# SCHEMATIC.net
KiCad netlist of a schematic drawn in Altium Designer
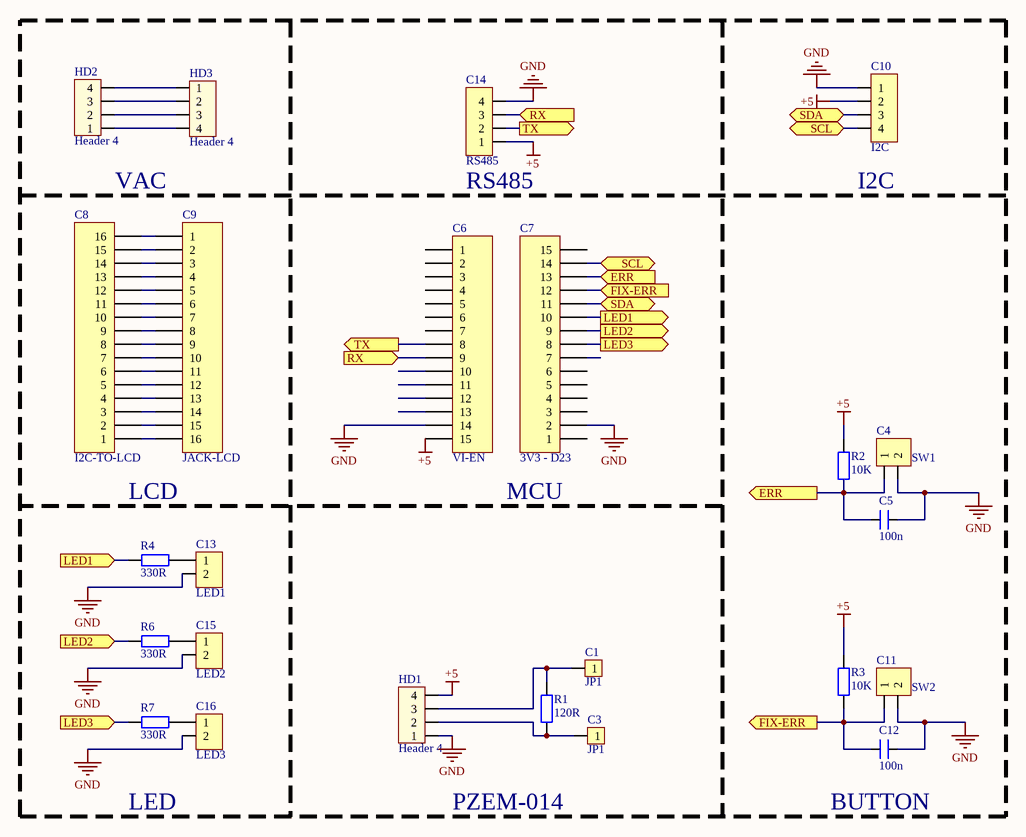
[diagram p0: SCHEMATIC.SchDoc]

(export (version "E")
  (design (tool "Eeschema 10.0.6"))
  (components
    (comp (ref "C1")
      (value "JP1")
      (footprint "JP1-D1T")
      (description "WR-PHD 2.54 mm Angled Socket Header")
      (fields
        (field (name "MANUFACTURER") "Würth Elektronik eiSos GmbH")
        (field (name "PARTNO") "613002143121")
        (field (name "CREATED BY") "Karrer Zheng")
      )
      (libsource (lib "LIBRARY") (part "JP1"))
    )
    (comp (ref "C3")
      (value "JP1")
      (footprint "JP1-D1T")
      (description "WR-PHD 2.54 mm Angled Socket Header")
      (fields
        (field (name "MANUFACTURER") "Würth Elektronik eiSos GmbH")
        (field (name "PARTNO") "613002143121")
        (field (name "CREATED BY") "Karrer Zheng")
      )
      (libsource (lib "LIBRARY") (part "JP1"))
    )
    (comp (ref "C4")
      (value "SW1")
      (footprint "Header2")
      (description "Header IDC, 2 x 1 Pin Vertical 2.54mm Pitch (Non-Boxed, Male)")
      (fields
        (field (name "MANUFACTURER") "Würth Elektronik eiSos GmbH")
        (field (name "PARTNO") "613002143121")
        (field (name "CREATED BY") "Karrer Zheng")
      )
      (libsource (lib "LIBRARY") (part "Header2"))
    )
    (comp (ref "C5")
      (value "100n")
      (footprint "SM-0805")
      (description "Cap SMD")
      (libsource (lib "echipkool-com-library") (part "CM"))
    )
    (comp (ref "C6")
      (value "VI-EN")
      (footprint "JP15-C1T")
      (description "WR-PHD 2.54 mm Angled Socket Header")
      (fields
        (field (name "MANUFACTURER") "Würth Elektronik eiSos GmbH")
        (field (name "PARTNO") "613015143121")
        (field (name "CREATED BY") "Karrer Zheng")
      )
      (libsource (lib "") (part "JP15_1"))
    )
    (comp (ref "C7")
      (value "3V3 - D23")
      (footprint "JP15-C1T")
      (description "WR-PHD 2.54 mm Angled Socket Header")
      (fields
        (field (name "MANUFACTURER") "Würth Elektronik eiSos GmbH")
        (field (name "PARTNO") "613015143121")
        (field (name "CREATED BY") "Karrer Zheng")
      )
      (libsource (lib "LIBRARY") (part "JP15"))
    )
    (comp (ref "C8")
      (value "I2C-TO-LCD")
      (footprint "JP16-C1T")
      (description "WR-PHD 2.54 mm Angled Socket Header")
      (fields
        (field (name "MANUFACTURER") "Würth Elektronik eiSos GmbH")
        (field (name "PARTNO") "613016143121")
        (field (name "CREATED BY") "Karrer Zheng")
      )
      (libsource (lib "") (part "JP16_1"))
    )
    (comp (ref "C9")
      (value "JACK-LCD")
      (footprint "JP16-C1T")
      (description "WR-PHD 2.54 mm Angled Socket Header")
      (fields
        (field (name "MANUFACTURER") "Würth Elektronik eiSos GmbH")
        (field (name "PARTNO") "613016143121")
        (field (name "CREATED BY") "Karrer Zheng")
      )
      (libsource (lib "LIBRARY") (part "JP16"))
    )
    (comp (ref "C10")
      (value "I2C")
      (footprint "JP4-C1T")
      (description "WR-PHD 2.54 mm Angled Socket Header")
      (fields
        (field (name "MANUFACTURER") "Würth Elektronik eiSos GmbH")
        (field (name "PARTNO") "613004143121")
        (field (name "CREATED BY") "Karrer Zheng")
      )
      (libsource (lib "") (part "JP4_1"))
    )
    (comp (ref "C11")
      (value "SW2")
      (footprint "Header2")
      (description "Header IDC, 2 x 1 Pin Vertical 2.54mm Pitch (Non-Boxed, Male)")
      (fields
        (field (name "MANUFACTURER") "Würth Elektronik eiSos GmbH")
        (field (name "PARTNO") "613002143121")
        (field (name "CREATED BY") "Karrer Zheng")
      )
      (libsource (lib "LIBRARY") (part "Header2"))
    )
    (comp (ref "C12")
      (value "100n")
      (footprint "SM-0805")
      (description "Cap SMD")
      (libsource (lib "echipkool-com-library") (part "CM"))
    )
    (comp (ref "C13")
      (value "LED1")
      (footprint "Header2")
      (description "Header IDC, 2 x 1 Pin Vertical 2.54mm Pitch (Non-Boxed, Male)")
      (fields
        (field (name "MANUFACTURER") "Würth Elektronik eiSos GmbH")
        (field (name "PARTNO") "613002143121")
        (field (name "CREATED BY") "Karrer Zheng")
      )
      (libsource (lib "") (part "Header2_1"))
    )
    (comp (ref "C14")
      (value "RS485")
      (footprint "JP4-C1T")
      (description "WR-PHD 2.54 mm Angled Socket Header")
      (fields
        (field (name "MANUFACTURER") "Würth Elektronik eiSos GmbH")
        (field (name "PARTNO") "613004143121")
        (field (name "CREATED BY") "Karrer Zheng")
      )
      (libsource (lib "LIBRARY") (part "JP4"))
    )
    (comp (ref "C15")
      (value "LED2")
      (footprint "Header2")
      (description "Header IDC, 2 x 1 Pin Vertical 2.54mm Pitch (Non-Boxed, Male)")
      (fields
        (field (name "MANUFACTURER") "Würth Elektronik eiSos GmbH")
        (field (name "PARTNO") "613002143121")
        (field (name "CREATED BY") "Karrer Zheng")
      )
      (libsource (lib "") (part "Header2_1"))
    )
    (comp (ref "C16")
      (value "LED3")
      (footprint "Header2")
      (description "Header IDC, 2 x 1 Pin Vertical 2.54mm Pitch (Non-Boxed, Male)")
      (fields
        (field (name "MANUFACTURER") "Würth Elektronik eiSos GmbH")
        (field (name "PARTNO") "613002143121")
        (field (name "CREATED BY") "Karrer Zheng")
      )
      (libsource (lib "") (part "Header2_1"))
    )
    (comp (ref "HD1")
      (value "Header 4")
      (footprint "HED4")
      (description "Header 4 (Green)")
      (libsource (lib "syhaunguyen") (part "Hed4"))
    )
    (comp (ref "HD2")
      (value "Header 4")
      (footprint "HED4")
      (description "Header 4 (Green)")
      (libsource (lib "syhaunguyen") (part "Hed4"))
    )
    (comp (ref "HD3")
      (value "Header 4")
      (footprint "HED4T")
      (description "Header 4 (Green)")
      (libsource (lib "") (part "Hed4_1"))
    )
    (comp (ref "R1")
      (value "120R")
      (footprint "SM-RES-0805")
      (description "Resistor 1/4W")
      (libsource (lib "echipkool-com-library") (part "R1/4W"))
    )
    (comp (ref "R2")
      (value "10K")
      (footprint "SM-RES-0805")
      (description "Resistor 1/4W")
      (libsource (lib "echipkool-com-library") (part "R1/4W"))
    )
    (comp (ref "R3")
      (value "10K")
      (footprint "SM-RES-0805")
      (description "Resistor 1/4W")
      (libsource (lib "echipkool-com-library") (part "R1/4W"))
    )
    (comp (ref "R4")
      (value "330R")
      (footprint "SM-RES-0805")
      (description "Resistor 1/4W")
      (libsource (lib "echipkool-com-library") (part "R1/4W"))
    )
    (comp (ref "R6")
      (value "330R")
      (footprint "SM-RES-0805")
      (description "Resistor 1/4W")
      (libsource (lib "echipkool-com-library") (part "R1/4W"))
    )
    (comp (ref "R7")
      (value "330R")
      (footprint "SM-RES-0805")
      (description "Resistor 1/4W")
      (libsource (lib "echipkool-com-library") (part "R1/4W"))
    )
  )
  (nets
    (net (code "1") (name "+5") (class "Default")
      (node (ref "C10") (pin "2") (pinfunction "2_2") (pintype "passive"))
      (node (ref "C14") (pin "1") (pinfunction "1_1") (pintype "passive"))
      (node (ref "C6") (pin "15") (pinfunction "15_15") (pintype "passive"))
      (node (ref "HD1") (pin "4") (pinfunction "4_4") (pintype "passive"))
      (node (ref "R2") (pin "1") (pinfunction "1_1") (pintype "passive"))
      (node (ref "R3") (pin "1") (pinfunction "1_1") (pintype "passive"))
    )
    (net (code "2") (name "/ERR") (class "Default")
      (node (ref "C4") (pin "1") (pinfunction "1_1") (pintype "passive"))
      (node (ref "C5") (pin "2") (pinfunction "2_2") (pintype "passive"))
      (node (ref "C7") (pin "13") (pinfunction "13_13") (pintype "passive"))
      (node (ref "R2") (pin "2") (pinfunction "2_2") (pintype "passive"))
    )
    (net (code "3") (name "/FIX-ERR") (class "Default")
      (node (ref "C11") (pin "1") (pinfunction "1_1") (pintype "passive"))
      (node (ref "C12") (pin "2") (pinfunction "2_2") (pintype "passive"))
      (node (ref "C7") (pin "12") (pinfunction "12_12") (pintype "passive"))
      (node (ref "R3") (pin "2") (pinfunction "2_2") (pintype "passive"))
    )
    (net (code "4") (name "/LED1") (class "Default")
      (node (ref "C7") (pin "10") (pinfunction "10_10") (pintype "passive"))
      (node (ref "R4") (pin "1") (pinfunction "1_1") (pintype "passive"))
    )
    (net (code "5") (name "/LED2") (class "Default")
      (node (ref "C7") (pin "9") (pinfunction "9_9") (pintype "passive"))
      (node (ref "R6") (pin "1") (pinfunction "1_1") (pintype "passive"))
    )
    (net (code "6") (name "/LED3") (class "Default")
      (node (ref "C7") (pin "8") (pinfunction "8_8") (pintype "passive"))
      (node (ref "R7") (pin "1") (pinfunction "1_1") (pintype "passive"))
    )
    (net (code "7") (name "/RX") (class "Default")
      (node (ref "C14") (pin "3") (pinfunction "3_3") (pintype "passive"))
      (node (ref "C6") (pin "9") (pinfunction "9_9") (pintype "passive"))
    )
    (net (code "8") (name "/SCL") (class "Default")
      (node (ref "C10") (pin "4") (pinfunction "4_4") (pintype "passive"))
      (node (ref "C7") (pin "14") (pinfunction "14_14") (pintype "passive"))
    )
    (net (code "9") (name "/SDA") (class "Default")
      (node (ref "C10") (pin "3") (pinfunction "3_3") (pintype "passive"))
      (node (ref "C7") (pin "11") (pinfunction "11_11") (pintype "passive"))
    )
    (net (code "10") (name "/TX") (class "Default")
      (node (ref "C14") (pin "2") (pinfunction "2_2") (pintype "passive"))
      (node (ref "C6") (pin "8") (pinfunction "8_8") (pintype "passive"))
    )
    (net (code "11") (name "GND") (class "Default")
      (node (ref "C10") (pin "1") (pinfunction "1_1") (pintype "passive"))
      (node (ref "C11") (pin "2") (pinfunction "2_2") (pintype "passive"))
      (node (ref "C12") (pin "1") (pinfunction "1_1") (pintype "passive"))
      (node (ref "C13") (pin "2") (pinfunction "2_2") (pintype "passive"))
      (node (ref "C14") (pin "4") (pinfunction "4_4") (pintype "passive"))
      (node (ref "C15") (pin "2") (pinfunction "2_2") (pintype "passive"))
      (node (ref "C16") (pin "2") (pinfunction "2_2") (pintype "passive"))
      (node (ref "C4") (pin "2") (pinfunction "2_2") (pintype "passive"))
      (node (ref "C5") (pin "1") (pinfunction "1_1") (pintype "passive"))
      (node (ref "C6") (pin "14") (pinfunction "14_14") (pintype "passive"))
      (node (ref "C7") (pin "2") (pinfunction "2_2") (pintype "passive"))
      (node (ref "HD1") (pin "1") (pinfunction "1_1") (pintype "passive"))
    )
    (net (code "12") (name "Net-(C1-Pad1)") (class "Default")
      (node (ref "C1") (pin "1") (pinfunction "1_1") (pintype "passive"))
      (node (ref "HD1") (pin "3") (pinfunction "3_3") (pintype "passive"))
      (node (ref "R1") (pin "1") (pinfunction "1_1") (pintype "passive"))
    )
    (net (code "13") (name "Net-(C3-Pad1)") (class "Default")
      (node (ref "C3") (pin "1") (pinfunction "1_1") (pintype "passive"))
      (node (ref "HD1") (pin "2") (pinfunction "2_2") (pintype "passive"))
      (node (ref "R1") (pin "2") (pinfunction "2_2") (pintype "passive"))
    )
    (net (code "14") (name "Net-(C8-Pad1)") (class "Default")
      (node (ref "C8") (pin "1") (pinfunction "1_1") (pintype "passive"))
      (node (ref "C9") (pin "16") (pinfunction "16_16") (pintype "passive"))
    )
    (net (code "15") (name "Net-(C8-Pad2)") (class "Default")
      (node (ref "C8") (pin "2") (pinfunction "2_2") (pintype "passive"))
      (node (ref "C9") (pin "15") (pinfunction "15_15") (pintype "passive"))
    )
    (net (code "16") (name "Net-(C8-Pad3)") (class "Default")
      (node (ref "C8") (pin "3") (pinfunction "3_3") (pintype "passive"))
      (node (ref "C9") (pin "14") (pinfunction "14_14") (pintype "passive"))
    )
    (net (code "17") (name "Net-(C8-Pad4)") (class "Default")
      (node (ref "C8") (pin "4") (pinfunction "4_4") (pintype "passive"))
      (node (ref "C9") (pin "13") (pinfunction "13_13") (pintype "passive"))
    )
    (net (code "18") (name "Net-(C8-Pad5)") (class "Default")
      (node (ref "C8") (pin "5") (pinfunction "5_5") (pintype "passive"))
      (node (ref "C9") (pin "12") (pinfunction "12_12") (pintype "passive"))
    )
    (net (code "19") (name "Net-(C8-Pad6)") (class "Default")
      (node (ref "C8") (pin "6") (pinfunction "6_6") (pintype "passive"))
      (node (ref "C9") (pin "11") (pinfunction "11_11") (pintype "passive"))
    )
    (net (code "20") (name "Net-(C8-Pad7)") (class "Default")
      (node (ref "C8") (pin "7") (pinfunction "7_7") (pintype "passive"))
      (node (ref "C9") (pin "10") (pinfunction "10_10") (pintype "passive"))
    )
    (net (code "21") (name "Net-(C8-Pad8)") (class "Default")
      (node (ref "C8") (pin "8") (pinfunction "8_8") (pintype "passive"))
      (node (ref "C9") (pin "9") (pinfunction "9_9") (pintype "passive"))
    )
    (net (code "22") (name "Net-(C8-Pad9)") (class "Default")
      (node (ref "C8") (pin "9") (pinfunction "9_9") (pintype "passive"))
      (node (ref "C9") (pin "8") (pinfunction "8_8") (pintype "passive"))
    )
    (net (code "23") (name "Net-(C8-Pad10)") (class "Default")
      (node (ref "C8") (pin "10") (pinfunction "10_10") (pintype "passive"))
      (node (ref "C9") (pin "7") (pinfunction "7_7") (pintype "passive"))
    )
    (net (code "24") (name "Net-(C8-Pad11)") (class "Default")
      (node (ref "C8") (pin "11") (pinfunction "11_11") (pintype "passive"))
      (node (ref "C9") (pin "6") (pinfunction "6_6") (pintype "passive"))
    )
    (net (code "25") (name "Net-(C8-Pad12)") (class "Default")
      (node (ref "C8") (pin "12") (pinfunction "12_12") (pintype "passive"))
      (node (ref "C9") (pin "5") (pinfunction "5_5") (pintype "passive"))
    )
    (net (code "26") (name "Net-(C8-Pad13)") (class "Default")
      (node (ref "C8") (pin "13") (pinfunction "13_13") (pintype "passive"))
      (node (ref "C9") (pin "4") (pinfunction "4_4") (pintype "passive"))
    )
    (net (code "27") (name "Net-(C8-Pad14)") (class "Default")
      (node (ref "C8") (pin "14") (pinfunction "14_14") (pintype "passive"))
      (node (ref "C9") (pin "3") (pinfunction "3_3") (pintype "passive"))
    )
    (net (code "28") (name "Net-(C8-Pad15)") (class "Default")
      (node (ref "C8") (pin "15") (pinfunction "15_15") (pintype "passive"))
      (node (ref "C9") (pin "2") (pinfunction "2_2") (pintype "passive"))
    )
    (net (code "29") (name "Net-(C8-Pad16)") (class "Default")
      (node (ref "C8") (pin "16") (pinfunction "16_16") (pintype "passive"))
      (node (ref "C9") (pin "1") (pinfunction "1_1") (pintype "passive"))
    )
    (net (code "30") (name "Net-(C13-Pad1)") (class "Default")
      (node (ref "C13") (pin "1") (pinfunction "1_1") (pintype "passive"))
      (node (ref "R4") (pin "2") (pinfunction "2_2") (pintype "passive"))
    )
    (net (code "31") (name "Net-(C15-Pad1)") (class "Default")
      (node (ref "C15") (pin "1") (pinfunction "1_1") (pintype "passive"))
      (node (ref "R6") (pin "2") (pinfunction "2_2") (pintype "passive"))
    )
    (net (code "32") (name "Net-(C16-Pad1)") (class "Default")
      (node (ref "C16") (pin "1") (pinfunction "1_1") (pintype "passive"))
      (node (ref "R7") (pin "2") (pinfunction "2_2") (pintype "passive"))
    )
    (net (code "33") (name "Net-(HD2-Pad1)") (class "Default")
      (node (ref "HD2") (pin "1") (pinfunction "1_1") (pintype "passive"))
      (node (ref "HD3") (pin "4") (pinfunction "4_4") (pintype "passive"))
    )
    (net (code "34") (name "Net-(HD2-Pad2)") (class "Default")
      (node (ref "HD2") (pin "2") (pinfunction "2_2") (pintype "passive"))
      (node (ref "HD3") (pin "3") (pinfunction "3_3") (pintype "passive"))
    )
    (net (code "35") (name "Net-(HD2-Pad3)") (class "Default")
      (node (ref "HD2") (pin "3") (pinfunction "3_3") (pintype "passive"))
      (node (ref "HD3") (pin "2") (pinfunction "2_2") (pintype "passive"))
    )
    (net (code "36") (name "Net-(HD2-Pad4)") (class "Default")
      (node (ref "HD2") (pin "4") (pinfunction "4_4") (pintype "passive"))
      (node (ref "HD3") (pin "1") (pinfunction "1_1") (pintype "passive"))
    )
    (net (code "37") (name "unconnected-(C6-Pad1)") (class "Default")
      (node (ref "C6") (pin "1") (pinfunction "1_1") (pintype "passive"))
    )
    (net (code "38") (name "unconnected-(C6-Pad2)") (class "Default")
      (node (ref "C6") (pin "2") (pinfunction "2_2") (pintype "passive"))
    )
    (net (code "39") (name "unconnected-(C6-Pad3)") (class "Default")
      (node (ref "C6") (pin "3") (pinfunction "3_3") (pintype "passive"))
    )
    (net (code "40") (name "unconnected-(C6-Pad4)") (class "Default")
      (node (ref "C6") (pin "4") (pinfunction "4_4") (pintype "passive"))
    )
    (net (code "41") (name "unconnected-(C6-Pad5)") (class "Default")
      (node (ref "C6") (pin "5") (pinfunction "5_5") (pintype "passive"))
    )
    (net (code "42") (name "unconnected-(C6-Pad6)") (class "Default")
      (node (ref "C6") (pin "6") (pinfunction "6_6") (pintype "passive"))
    )
    (net (code "43") (name "unconnected-(C6-Pad7)") (class "Default")
      (node (ref "C6") (pin "7") (pinfunction "7_7") (pintype "passive"))
    )
    (net (code "44") (name "unconnected-(C6-Pad10)") (class "Default")
      (node (ref "C6") (pin "10") (pinfunction "10_10") (pintype "passive"))
    )
    (net (code "45") (name "unconnected-(C6-Pad11)") (class "Default")
      (node (ref "C6") (pin "11") (pinfunction "11_11") (pintype "passive"))
    )
    (net (code "46") (name "unconnected-(C6-Pad12)") (class "Default")
      (node (ref "C6") (pin "12") (pinfunction "12_12") (pintype "passive"))
    )
    (net (code "47") (name "unconnected-(C6-Pad13)") (class "Default")
      (node (ref "C6") (pin "13") (pinfunction "13_13") (pintype "passive"))
    )
    (net (code "48") (name "unconnected-(C7-Pad1)") (class "Default")
      (node (ref "C7") (pin "1") (pinfunction "1_1") (pintype "passive"))
    )
    (net (code "49") (name "unconnected-(C7-Pad3)") (class "Default")
      (node (ref "C7") (pin "3") (pinfunction "3_3") (pintype "passive"))
    )
    (net (code "50") (name "unconnected-(C7-Pad4)") (class "Default")
      (node (ref "C7") (pin "4") (pinfunction "4_4") (pintype "passive"))
    )
    (net (code "51") (name "unconnected-(C7-Pad5)") (class "Default")
      (node (ref "C7") (pin "5") (pinfunction "5_5") (pintype "passive"))
    )
    (net (code "52") (name "unconnected-(C7-Pad6)") (class "Default")
      (node (ref "C7") (pin "6") (pinfunction "6_6") (pintype "passive"))
    )
    (net (code "53") (name "unconnected-(C7-Pad7)") (class "Default")
      (node (ref "C7") (pin "7") (pinfunction "7_7") (pintype "passive"))
    )
    (net (code "54") (name "unconnected-(C7-Pad15)") (class "Default")
      (node (ref "C7") (pin "15") (pinfunction "15_15") (pintype "passive"))
    )
  )
)
